# Pcb_Schemetic_Gas_Detector.net
KiCad netlist of a schematic drawn in Altium Designer
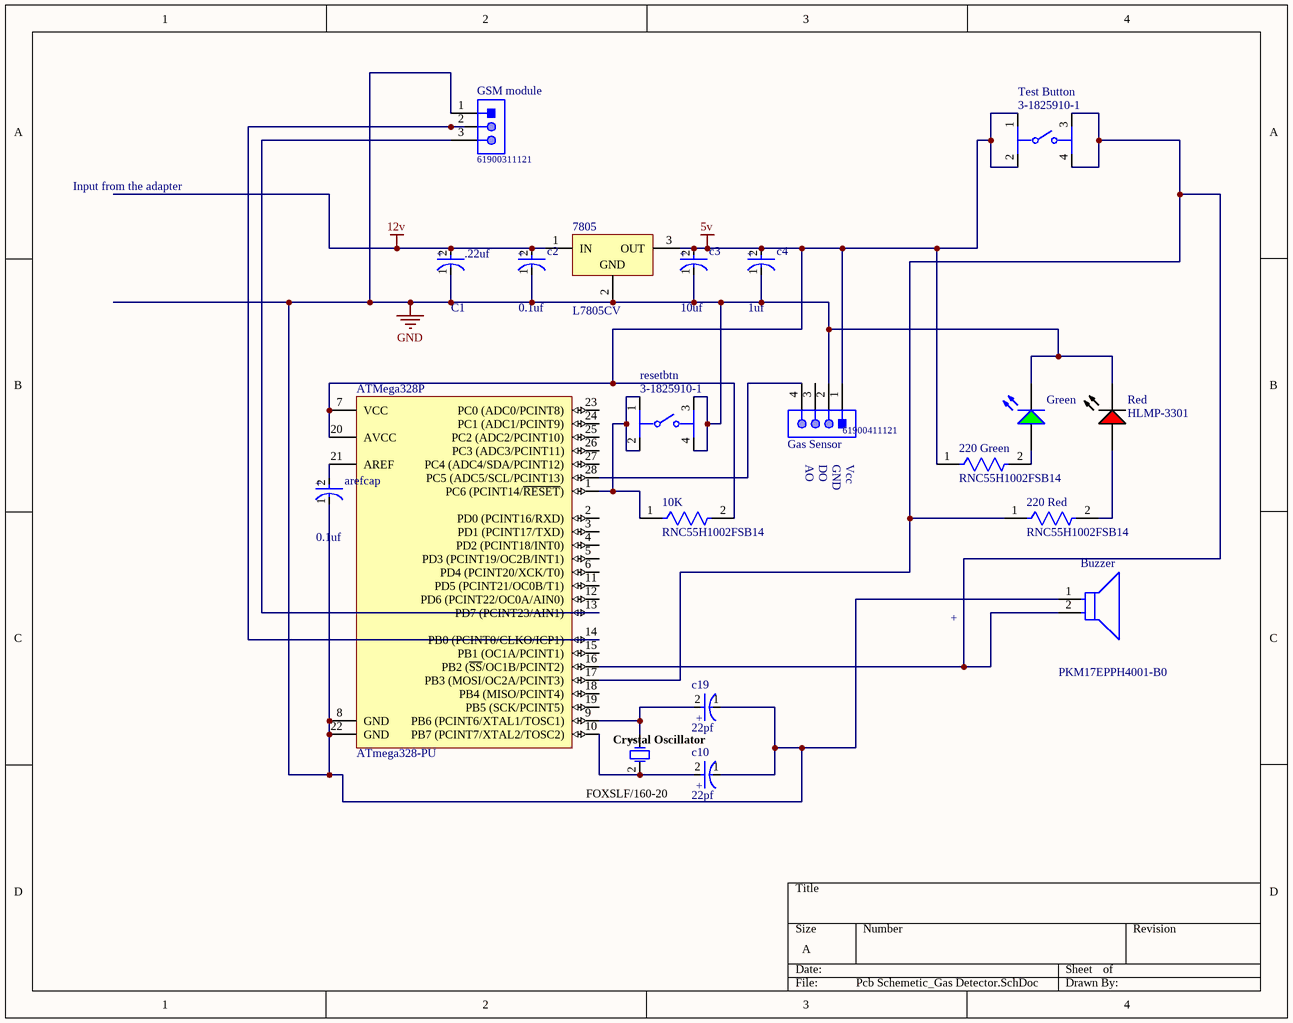
[diagram p0: Pcb Schemetic_Gas Detector.SchDoc]

(export (version "E")
  (design (tool "Eeschema 10.0.6"))
  (components
    (comp (ref ".22uf")
      (value "C1")
      (footprint "FP-RAD-TH-D_12_5_0_5-L_25-MFG")
      (description "Aluminum Electrolytic Capacitors (Radial Lead Type) 22uF ±20% 400V")
      (fields (field (name "TOLERANCE") "20%") (field (name "VOLTAGE") "400V"))
      (libsource (lib "Altium Content Vault") (part "203bc49f2ac43e59fd269a8c329ed05"))
    )
    (comp (ref "10K")
      (value "RNC55H1002FSB14")
      (footprint "FP-RNC55-MFG")
      (description "RES 10K OHM 1/8W 1% AXIAL")
      (fields
        (field (name "TOLERANCE") "1%")
        (field (name "OCTOPART") "https://octopart.com/rnc55h1002fs-vishay-40848808")
      )
      (libsource (lib "Altium Content Vault") (part "1029c3af85768c4190bb7ad29bc67b5"))
    )
    (comp (ref "220 Green")
      (value "RNC55H1002FSB14")
      (footprint "FP-RNC55-MFG")
      (description "RES 10K OHM 1/8W 1% AXIAL")
      (fields
        (field (name "TOLERANCE") "1%")
        (field (name "OCTOPART") "https://octopart.com/rnc55h1002fs-vishay-40848808")
      )
      (libsource (lib "Altium Content Vault") (part "1029c3af85768c4190bb7ad29bc67b5"))
    )
    (comp (ref "220 Red")
      (value "RNC55H1002FSB14")
      (footprint "FP-RNC55-MFG")
      (description "RES 10K OHM 1/8W 1% AXIAL")
      (fields
        (field (name "TOLERANCE") "1%")
        (field (name "OCTOPART") "https://octopart.com/rnc55h1002fs-vishay-40848808")
      )
      (libsource (lib "Altium Content Vault") (part "1029c3af85768c4190bb7ad29bc67b5"))
    )
    (comp (ref "7805")
      (value "L7805CV")
      (footprint "TO220")
      (description "Positive Voltage Regulator, 5V, 3-Pin TO-220")
      (libsource (lib "Altium Content Vault") (part "PM-REG-L4940-SIL3"))
    )
    (comp (ref "arefcap")
      (value "0.1uf")
      (footprint "FP-RAD-TH-D_10_0_5-L_20_2-MFG")
      (description "Aluminum Electrolytic Capacitors (Radial Lead Type) 10uF ±20% 400V")
      (fields (field (name "TOLERANCE") "20%") (field (name "VOLTAGE") "400V"))
      (libsource (lib "Altium Content Vault") (part "203bc49f2ac43e59fd269a8c329ed05"))
    )
    (comp (ref "ATMega328P")
      (value "ATmega328-PU")
      (footprint "28P3")
      (libsource (lib "Altium Content Vault") (part "MC-8B-ATM48-IL28"))
    )
    (comp (ref "Buzzer")
      (value "PKM17EPPH4001-B0")
      (footprint "FP-PKM17EPPH4001-B0-MFG")
      (description "AUDIO PIEZO TRANSDUCER 25V TH")
      (libsource (lib "Altium Content Vault") (part "5f581d31613f872430949aa526fd155"))
    )
    (comp (ref "c2")
      (value "0.1uf")
      (footprint "FP-RAD-TH-D_10_0_5-L_20_2-MFG")
      (description "Aluminum Electrolytic Capacitors (Radial Lead Type) 10uF ±20% 400V")
      (fields (field (name "TOLERANCE") "20%") (field (name "VOLTAGE") "400V"))
      (libsource (lib "Altium Content Vault") (part "203bc49f2ac43e59fd269a8c329ed05"))
    )
    (comp (ref "c3")
      (value "10uf")
      (footprint "FP-RAD-TH-D_10_0_5-L_20_2-MFG")
      (description "Aluminum Electrolytic Capacitors (Radial Lead Type) 10uF ±20% 400V")
      (fields (field (name "TOLERANCE") "20%") (field (name "VOLTAGE") "400V"))
      (libsource (lib "Altium Content Vault") (part "203bc49f2ac43e59fd269a8c329ed05"))
    )
    (comp (ref "c4")
      (value "1uf")
      (footprint "FP-RAD-TH-D_10_0_5-L_20_2-MFG")
      (description "Aluminum Electrolytic Capacitors (Radial Lead Type) 10uF ±20% 400V")
      (fields (field (name "TOLERANCE") "20%") (field (name "VOLTAGE") "400V"))
      (libsource (lib "Altium Content Vault") (part "203bc49f2ac43e59fd269a8c329ed05"))
    )
    (comp (ref "c10")
      (value "22pf")
      (footprint "FP-RAD-TH-D_10_0_5-L_20_2-MFG")
      (description "Aluminum Electrolytic Capacitors (Radial Lead Type) 10uF ±20% 400V")
      (fields (field (name "TOLERANCE") "20%") (field (name "VOLTAGE") "400V"))
      (libsource (lib "Altium Content Vault") (part "203bc49f2ac43e59fd269a8c329ed05"))
    )
    (comp (ref "c19")
      (value "22pf")
      (footprint "FP-RAD-TH-D_10_0_5-L_20_2-MFG")
      (description "Aluminum Electrolytic Capacitors (Radial Lead Type) 10uF ±20% 400V")
      (fields (field (name "TOLERANCE") "20%") (field (name "VOLTAGE") "400V"))
      (libsource (lib "Altium Content Vault") (part "203bc49f2ac43e59fd269a8c329ed05"))
    )
    (comp (ref "Crystal Oscillator")
      (value "FOXSLF/160-20")
      (footprint "FOX-FOXSLF160-20")
      (description "Resistance Weld Thru-Hole Crystal, 16 MHz, -20 to 70 degC, 2-Pin THD, RoHS, Bulk")
      (fields (field (name "TOLERANCE") "1%"))
      (libsource (lib "Altium Content Vault") (part "XTAL-1-2-2"))
    )
    (comp (ref "Gas Sensor")
      (value "61900411121")
      (footprint "61900411121")
      (description "Male Locking Header WR-WTB, THT, Vertical, pitch 2.54 mm, 1 x 4 position")
      (fields (field (name "MANUFACTURER") "Wurth Elektronik") (field (name "PUBLISHER") "WurthElektronik"))
      (libsource (lib "Altium Content Vault") (part "WE-CN-1P-M-R4"))
    )
    (comp (ref "Green")
      (value "~")
      (footprint "AVAG-HLMP-3507")
      (description "T-1 3/4 (5 mm) Diffused LED Lamp, Green, 2.1 V, -20 to 100 degC, 2-Pin THD, RoHS, Bulk")
      (fields (field (name "MANUFACTURER") "Avago"))
      (libsource (lib "Altium Content Vault") (part "LED-GREEN-AK-2"))
    )
    (comp (ref "GSM module")
      (value "61900311121")
      (footprint "61900311121")
      (description "Male Locking Header WR-WTB, THT, Vertical, pitch 2.54 mm, 1 x 3 position")
      (fields (field (name "MANUFACTURER") "Wurth Elektronik") (field (name "PUBLISHER") "WurthElektronik"))
      (libsource (lib "Altium Content Vault") (part "WE-CN-1P-M-R3"))
    )
    (comp (ref "Red")
      (value "HLMP-3301")
      (footprint "AVAG-HLMP-3301-2")
      (description "T-1 3/4 (5 mm) Diffused LED Lamp, 1.9 V, -40 to 100 degC, 2-Pin THD, RoHS, Bulk")
      (fields (field (name "MANUFACTURER") "Avago"))
      (libsource (lib "Altium Content Vault") (part "LED-RED-K1A2-2"))
    )
    (comp (ref "resetbtn")
      (value "3-1825910-1")
      (footprint "FP-3-1825910-1-MFG")
      (description "SWITCH TACTILE SPST-NO 0.05A 24V")
      (fields
        (field (name "MANUFACTURER") "TE Connectivity")
        (field (name "OCTOPART") "https://octopart.com/3-1825910-1-te+connectivity-46506874")
      )
      (libsource (lib "Altium Content Vault") (part "b8895f3f4cefb76e1819d2863dba89b"))
    )
    (comp (ref "Test Button")
      (value "3-1825910-1")
      (footprint "FP-3-1825910-1-MFG")
      (description "SWITCH TACTILE SPST-NO 0.05A 24V")
      (fields
        (field (name "MANUFACTURER") "TE Connectivity")
        (field (name "OCTOPART") "https://octopart.com/3-1825910-1-te+connectivity-46506874")
      )
      (libsource (lib "Altium Content Vault") (part "b8895f3f4cefb76e1819d2863dba89b"))
    )
  )
  (nets
    (net (code "1") (name "5v") (class "Default")
      (node (ref "10K") (pin "2") (pinfunction "2_2") (pintype "passive"))
      (node (ref "220 Green") (pin "1") (pinfunction "1_1") (pintype "passive"))
      (node (ref "7805") (pin "3") (pinfunction "OUT_3") (pintype "power_in"))
      (node (ref "ATMega328P") (pin "20") (pinfunction "AVCC_20") (pintype "power_in"))
      (node (ref "ATMega328P") (pin "7") (pinfunction "VCC_7") (pintype "power_in"))
      (node (ref "Gas Sensor") (pin "1") (pinfunction "1_1") (pintype "passive"))
      (node (ref "Test Button") (pin "1") (pinfunction "1_1") (pintype "passive"))
      (node (ref "Test Button") (pin "2") (pinfunction "2_2") (pintype "passive"))
      (node (ref "c3") (pin "2") (pinfunction "A_2") (pintype "passive"))
      (node (ref "c4") (pin "2") (pinfunction "A_2") (pintype "passive"))
    )
    (net (code "2") (name "12v") (class "Default")
      (node (ref ".22uf") (pin "2") (pinfunction "A_2") (pintype "passive"))
      (node (ref "7805") (pin "1") (pinfunction "IN_1") (pintype "power_in"))
      (node (ref "c2") (pin "2") (pinfunction "A_2") (pintype "passive"))
    )
    (net (code "3") (name "GND") (class "Default")
      (node (ref ".22uf") (pin "1") (pinfunction "C_1") (pintype "passive"))
      (node (ref "7805") (pin "2") (pinfunction "GND_2") (pintype "power_in"))
      (node (ref "ATMega328P") (pin "22") (pinfunction "GND_22") (pintype "power_in"))
      (node (ref "ATMega328P") (pin "8") (pinfunction "GND_8") (pintype "power_in"))
      (node (ref "Buzzer") (pin "1") (pinfunction "1_1") (pintype "passive"))
      (node (ref "GSM module") (pin "1") (pinfunction "1_1") (pintype "passive"))
      (node (ref "Gas Sensor") (pin "2") (pinfunction "2_2") (pintype "passive"))
      (node (ref "Green") (pin "2") (pinfunction "K_2") (pintype "passive"))
      (node (ref "Red") (pin "1") (pinfunction "K_1") (pintype "passive"))
      (node (ref "arefcap") (pin "1") (pinfunction "C_1") (pintype "passive"))
      (node (ref "c10") (pin "1") (pinfunction "C_1") (pintype "passive"))
      (node (ref "c19") (pin "1") (pinfunction "C_1") (pintype "passive"))
      (node (ref "c2") (pin "1") (pinfunction "C_1") (pintype "passive"))
      (node (ref "c3") (pin "1") (pinfunction "C_1") (pintype "passive"))
      (node (ref "c4") (pin "1") (pinfunction "C_1") (pintype "passive"))
      (node (ref "resetbtn") (pin "3") (pinfunction "3_3") (pintype "passive"))
      (node (ref "resetbtn") (pin "4") (pinfunction "4_4") (pintype "passive"))
    )
    (net (code "4") (name "Net-(ATMega328P-AREF)") (class "Default")
      (node (ref "ATMega328P") (pin "21") (pinfunction "AREF_21") (pintype "power_in"))
      (node (ref "arefcap") (pin "2") (pinfunction "A_2") (pintype "passive"))
    )
    (net (code "5") (name "Net-(ATMega328P-PB0_(PCINT0{slash}CLKO{slash}ICP1))") (class "Default")
      (node (ref "ATMega328P") (pin "14") (pinfunction "PB0_(PCINT0/CLKO/ICP1)_14") (pintype "bidirectional"))
      (node (ref "GSM module") (pin "2") (pinfunction "2_2") (pintype "passive"))
    )
    (net (code "6") (name "Net-(ATMega328P-PB2_(~{SS}{slash}OC1B{slash}PCINT2))") (class "Default")
      (node (ref "220 Red") (pin "1") (pinfunction "1_1") (pintype "passive"))
      (node (ref "ATMega328P") (pin "16") (pinfunction "PB2_(~{SS}/OC1B/PCINT2)_16") (pintype "bidirectional"))
      (node (ref "ATMega328P") (pin "17") (pinfunction "PB3_(MOSI/OC2A/PCINT3)_17") (pintype "bidirectional"))
      (node (ref "Buzzer") (pin "2") (pinfunction "2_2") (pintype "passive"))
      (node (ref "Test Button") (pin "3") (pinfunction "3_3") (pintype "passive"))
      (node (ref "Test Button") (pin "4") (pinfunction "4_4") (pintype "passive"))
    )
    (net (code "7") (name "Net-(ATMega328P-PB6_(PCINT6{slash}XTAL1{slash}TOSC1))") (class "Default")
      (node (ref "ATMega328P") (pin "9") (pinfunction "PB6_(PCINT6/XTAL1/TOSC1)_9") (pintype "bidirectional"))
      (node (ref "Crystal Oscillator") (pin "1") (pinfunction "1_1") (pintype "passive"))
      (node (ref "c19") (pin "2") (pinfunction "A_2") (pintype "passive"))
    )
    (net (code "8") (name "Net-(ATMega328P-PB7_(PCINT7{slash}XTAL2{slash}TOSC2))") (class "Default")
      (node (ref "ATMega328P") (pin "10") (pinfunction "PB7_(PCINT7/XTAL2/TOSC2)_10") (pintype "bidirectional"))
      (node (ref "Crystal Oscillator") (pin "2") (pinfunction "2_2") (pintype "passive"))
      (node (ref "c10") (pin "2") (pinfunction "A_2") (pintype "passive"))
    )
    (net (code "9") (name "Net-(ATMega328P-PC5_(ADC5{slash}SCL{slash}PCINT13))") (class "Default")
      (node (ref "ATMega328P") (pin "28") (pinfunction "PC5_(ADC5/SCL/PCINT13)_28") (pintype "bidirectional"))
      (node (ref "Gas Sensor") (pin "4") (pinfunction "4_4") (pintype "passive"))
    )
    (net (code "10") (name "Net-(ATMega328P-PC6_(PCINT14{slash}~{RESET}))") (class "Default")
      (node (ref "10K") (pin "1") (pinfunction "1_1") (pintype "passive"))
      (node (ref "ATMega328P") (pin "1") (pinfunction "PC6_(PCINT14/~{RESET})_1") (pintype "bidirectional"))
      (node (ref "resetbtn") (pin "1") (pinfunction "1_1") (pintype "passive"))
      (node (ref "resetbtn") (pin "2") (pinfunction "2_2") (pintype "passive"))
    )
    (net (code "11") (name "Net-(ATMega328P-PD7_(PCINT23{slash}AIN1))") (class "Default")
      (node (ref "ATMega328P") (pin "13") (pinfunction "PD7_(PCINT23/AIN1)_13") (pintype "bidirectional"))
      (node (ref "GSM module") (pin "3") (pinfunction "3_3") (pintype "passive"))
    )
    (net (code "12") (name "Net-(Green-A)") (class "Default")
      (node (ref "220 Green") (pin "2") (pinfunction "2_2") (pintype "passive"))
      (node (ref "Green") (pin "1") (pinfunction "A_1") (pintype "passive"))
    )
    (net (code "13") (name "Net-(Red-A)") (class "Default")
      (node (ref "220 Red") (pin "2") (pinfunction "2_2") (pintype "passive"))
      (node (ref "Red") (pin "2") (pinfunction "A_2") (pintype "passive"))
    )
    (net (code "14") (name "unconnected-(ATMega328P-PB1_(OC1A{slash}PCINT1)-Pad15)") (class "Default")
      (node (ref "ATMega328P") (pin "15") (pinfunction "PB1_(OC1A/PCINT1)_15") (pintype "bidirectional"))
    )
    (net (code "15") (name "unconnected-(ATMega328P-PB4_(MISO{slash}PCINT4)-Pad18)") (class "Default")
      (node (ref "ATMega328P") (pin "18") (pinfunction "PB4_(MISO/PCINT4)_18") (pintype "bidirectional"))
    )
    (net (code "16") (name "unconnected-(ATMega328P-PB5_(SCK{slash}PCINT5)-Pad19)") (class "Default")
      (node (ref "ATMega328P") (pin "19") (pinfunction "PB5_(SCK/PCINT5)_19") (pintype "bidirectional"))
    )
    (net (code "17") (name "unconnected-(ATMega328P-PC0_(ADC0{slash}PCINT8)-Pad23)") (class "Default")
      (node (ref "ATMega328P") (pin "23") (pinfunction "PC0_(ADC0/PCINT8)_23") (pintype "bidirectional"))
    )
    (net (code "18") (name "unconnected-(ATMega328P-PC1_(ADC1{slash}PCINT9)-Pad24)") (class "Default")
      (node (ref "ATMega328P") (pin "24") (pinfunction "PC1_(ADC1/PCINT9)_24") (pintype "bidirectional"))
    )
    (net (code "19") (name "unconnected-(ATMega328P-PC2_(ADC2{slash}PCINT10)-Pad25)") (class "Default")
      (node (ref "ATMega328P") (pin "25") (pinfunction "PC2_(ADC2/PCINT10)_25") (pintype "bidirectional"))
    )
    (net (code "20") (name "unconnected-(ATMega328P-PC3_(ADC3{slash}PCINT11)-Pad26)") (class "Default")
      (node (ref "ATMega328P") (pin "26") (pinfunction "PC3_(ADC3/PCINT11)_26") (pintype "bidirectional"))
    )
    (net (code "21") (name "unconnected-(ATMega328P-PC4_(ADC4{slash}SDA{slash}PCINT12)-Pad27)") (class "Default")
      (node (ref "ATMega328P") (pin "27") (pinfunction "PC4_(ADC4/SDA/PCINT12)_27") (pintype "bidirectional"))
    )
    (net (code "22") (name "unconnected-(ATMega328P-PD0_(PCINT16{slash}RXD)-Pad2)") (class "Default")
      (node (ref "ATMega328P") (pin "2") (pinfunction "PD0_(PCINT16/RXD)_2") (pintype "bidirectional"))
    )
    (net (code "23") (name "unconnected-(ATMega328P-PD1_(PCINT17{slash}TXD)-Pad3)") (class "Default")
      (node (ref "ATMega328P") (pin "3") (pinfunction "PD1_(PCINT17/TXD)_3") (pintype "bidirectional"))
    )
    (net (code "24") (name "unconnected-(ATMega328P-PD2_(PCINT18{slash}INT0)-Pad4)") (class "Default")
      (node (ref "ATMega328P") (pin "4") (pinfunction "PD2_(PCINT18/INT0)_4") (pintype "bidirectional"))
    )
    (net (code "25") (name "unconnected-(ATMega328P-PD3_(PCINT19{slash}OC2B{slash}INT1)-Pad5)") (class "Default")
      (node (ref "ATMega328P") (pin "5") (pinfunction "PD3_(PCINT19/OC2B/INT1)_5") (pintype "bidirectional"))
    )
    (net (code "26") (name "unconnected-(ATMega328P-PD4_(PCINT20{slash}XCK{slash}T0)-Pad6)") (class "Default")
      (node (ref "ATMega328P") (pin "6") (pinfunction "PD4_(PCINT20/XCK/T0)_6") (pintype "bidirectional"))
    )
    (net (code "27") (name "unconnected-(ATMega328P-PD5_(PCINT21{slash}OC0B{slash}T1)-Pad11)") (class "Default")
      (node (ref "ATMega328P") (pin "11") (pinfunction "PD5_(PCINT21/OC0B/T1)_11") (pintype "bidirectional"))
    )
    (net (code "28") (name "unconnected-(ATMega328P-PD6_(PCINT22{slash}OC0A{slash}AIN0)-Pad12)") (class "Default")
      (node (ref "ATMega328P") (pin "12") (pinfunction "PD6_(PCINT22/OC0A/AIN0)_12") (pintype "bidirectional"))
    )
    (net (code "29") (name "unconnected-(Gas Sensor-Pad3)") (class "Default")
      (node (ref "Gas Sensor") (pin "3") (pinfunction "3_3") (pintype "passive"))
    )
  )
)
